# input_filter.net
KiCad netlist of a schematic drawn in Altium Designer
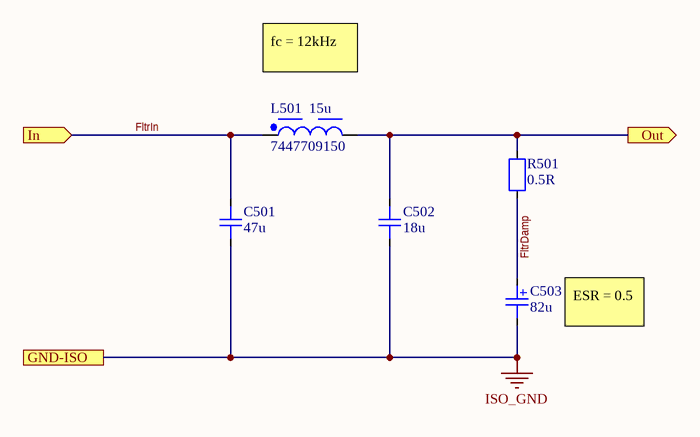
[diagram p0: input_filter.SchDoc]

(export (version "E")
  (design (tool "Eeschema 10.0.6"))
  (components
    (comp (ref "C501")
      (value "47u")
      (footprint "CAP2220")
      (description "810-C5750X7R1V476M23")
      (libsource (lib "schematic_library") (part "Capacitor"))
    )
    (comp (ref "C502")
      (value "18u")
      (footprint "CAP2220")
      (description "80-C2220C156K5R")
      (libsource (lib "schematic_library") (part "Capacitor"))
    )
    (comp (ref "C503")
      (value "82u")
      (footprint "WCAP-PSLC_D8H11.7")
      (libsource (lib "schematic_library") (part "Capacitor"))
    )
    (comp (ref "L501")
      (value "7447709150")
      (footprint "WE-PD_1210")
      (fields (field (name "TOLERANCE") "20%"))
      (libsource (lib "Altium Content Vault") (part "Inductor - 2"))
    )
    (comp (ref "R501")
      (value "0.5R")
      (footprint "RES0603")
      (libsource (lib "schematic_library") (part "Resistor"))
    )
  )
  (nets
    (net (code "1") (name "/FltrDamp") (class "Default")
      (node (ref "C503") (pin "1") (pintype "passive"))
      (node (ref "R501") (pin "2") (pintype "passive"))
    )
    (net (code "2") (name "/FltrIn") (class "Default")
      (node (ref "C501") (pin "1") (pintype "passive"))
      (node (ref "L501") (pin "1") (pinfunction "1_1") (pintype "passive"))
    )
    (net (code "3") (name "/Out") (class "Default")
      (node (ref "C502") (pin "1") (pintype "passive"))
      (node (ref "L501") (pin "2") (pinfunction "2_2") (pintype "passive"))
      (node (ref "R501") (pin "1") (pintype "passive"))
    )
    (net (code "4") (name "ISO_GND") (class "Default")
      (node (ref "C501") (pin "2") (pintype "passive"))
      (node (ref "C502") (pin "2") (pintype "passive"))
      (node (ref "C503") (pin "2") (pintype "passive"))
    )
  )
)
